# ni.net
KiCad netlist of a schematic drawn in EAGLE
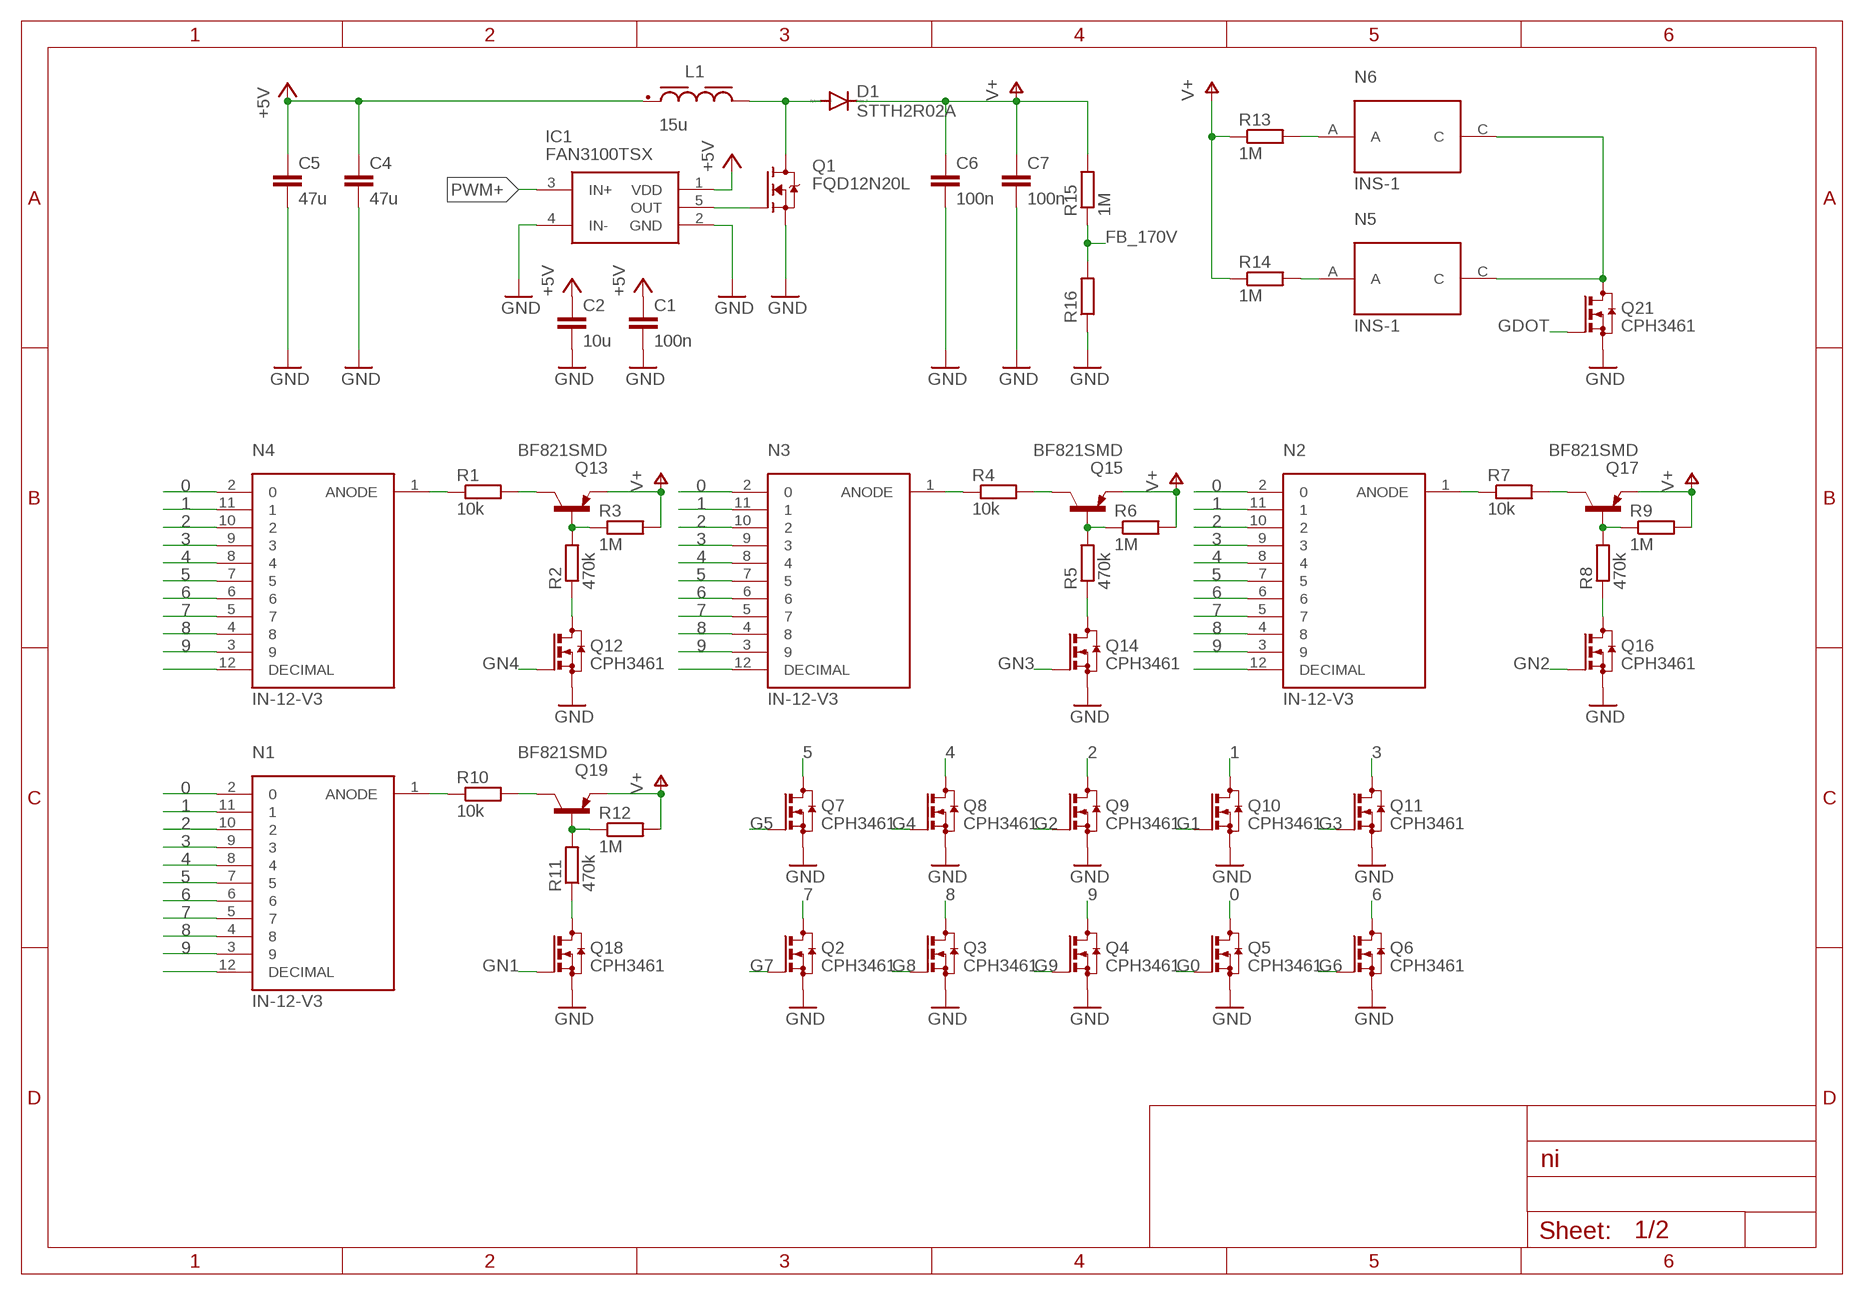
[diagram p0: schematic, sheet 1]
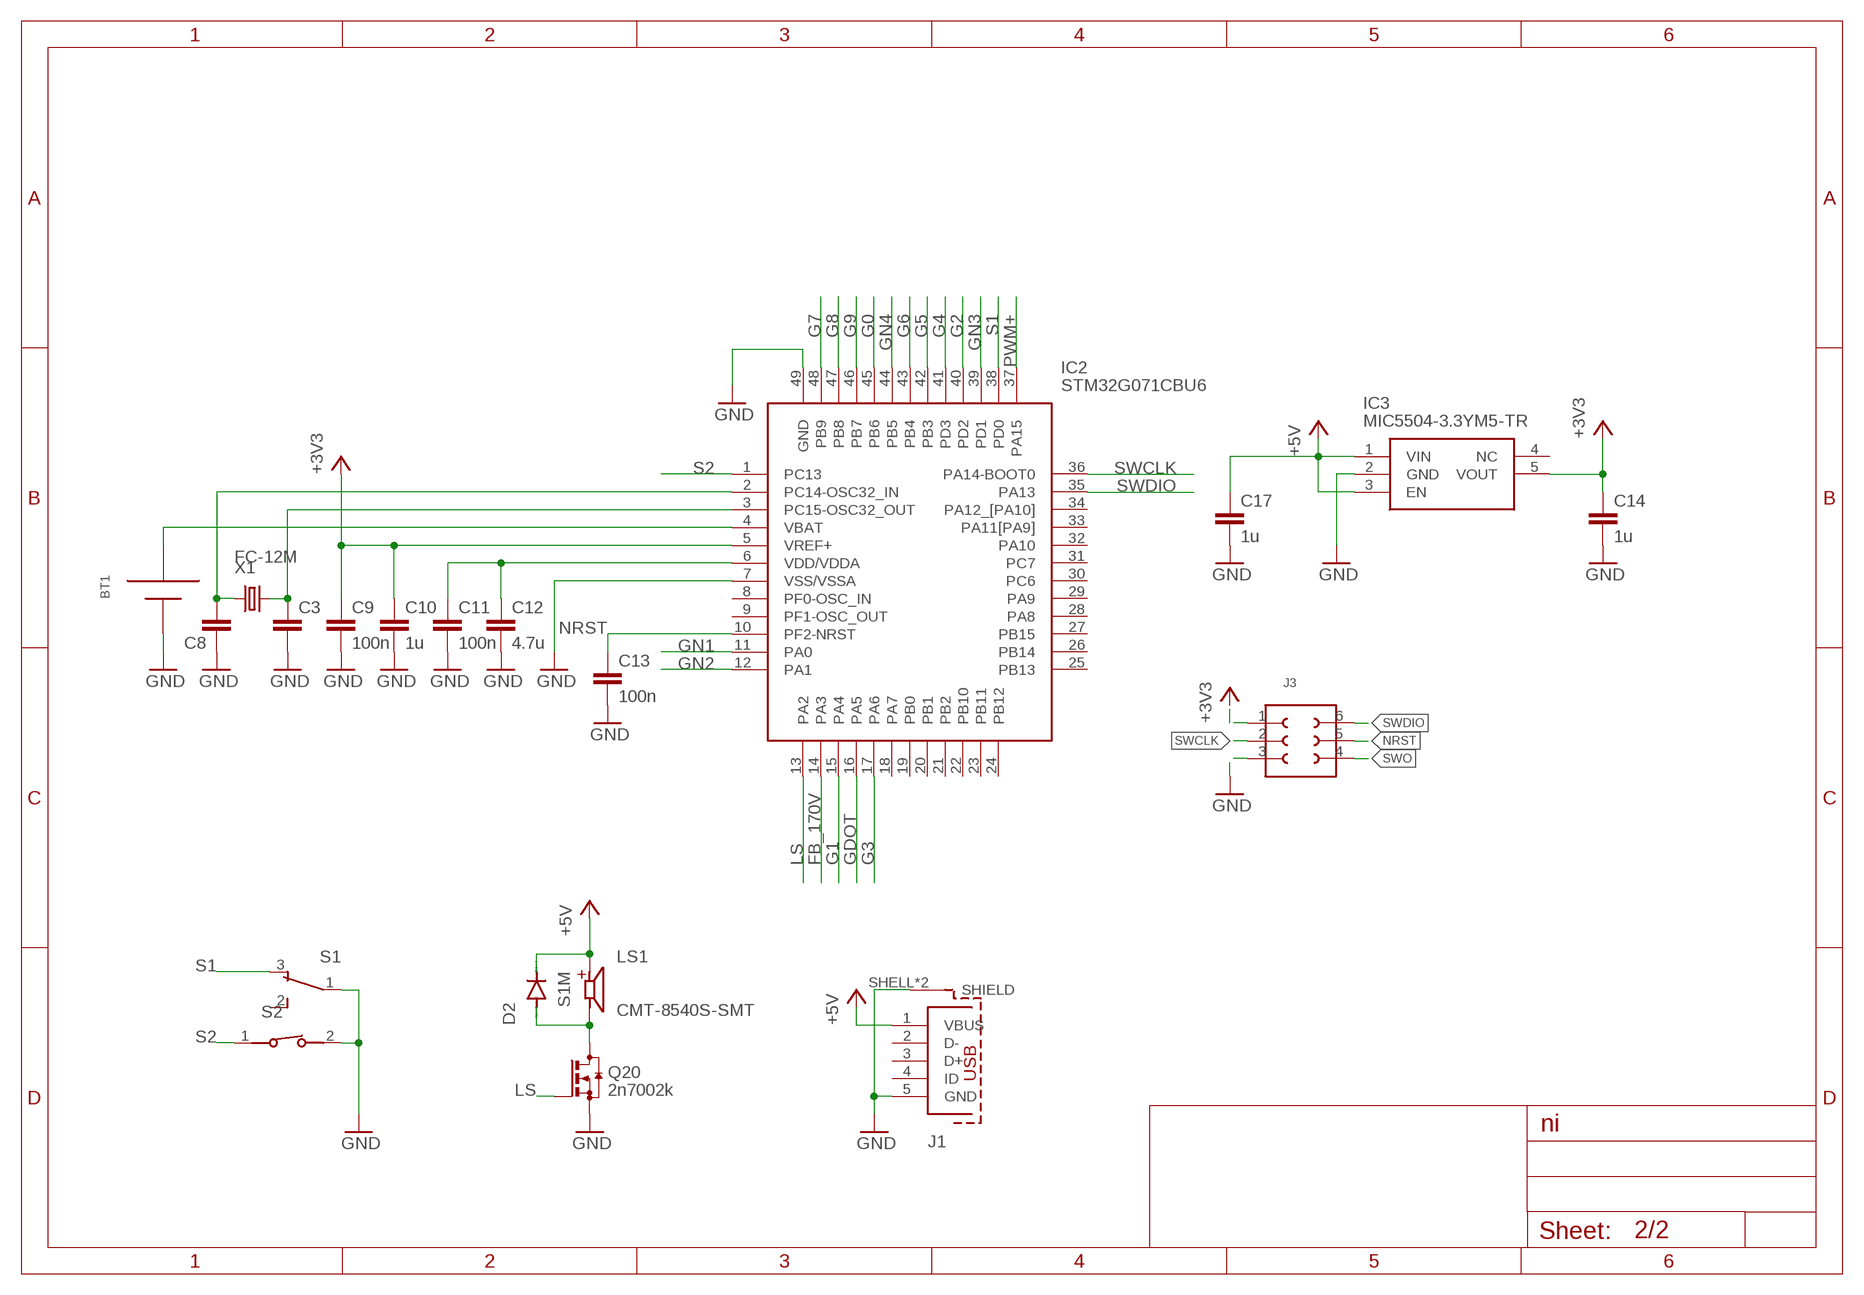
[diagram p1: schematic, sheet 2]

(export (version "E")
  (design (tool "Eeschema 10.0.6"))
  (components
    (comp (ref "BT1")
      (value "CR1225FH-LF")
      (footprint "eagle-import:CR1225FH-LF")
      (libsource (lib "eagle-import") (part "CR1225FH-LF"))
    )
    (comp (ref "C3")
      (value "C-EUC0402")
      (footprint "eagle-import:C0402")
      (libsource (lib "eagle-import") (part "C-EUC0402"))
    )
    (comp (ref "C8")
      (value "C-EUC0402")
      (footprint "eagle-import:C0402")
      (libsource (lib "eagle-import") (part "C-EUC0402"))
    )
    (comp (ref "C9")
      (value "100n")
      (footprint "eagle-import:C0402")
      (libsource (lib "eagle-import") (part "C-EUC0402"))
    )
    (comp (ref "C10")
      (value "1u")
      (footprint "eagle-import:C0402")
      (libsource (lib "eagle-import") (part "C-EUC0402"))
    )
    (comp (ref "C11")
      (value "100n")
      (footprint "eagle-import:C0402")
      (libsource (lib "eagle-import") (part "C-EUC0402"))
    )
    (comp (ref "C12")
      (value "4.7u")
      (footprint "eagle-import:C0402")
      (libsource (lib "eagle-import") (part "C-EUC0402"))
    )
    (comp (ref "C13")
      (value "100n")
      (footprint "eagle-import:C0402")
      (libsource (lib "eagle-import") (part "C-EUC0402"))
    )
    (comp (ref "C14")
      (value "1u")
      (footprint "eagle-import:C0402")
      (libsource (lib "eagle-import") (part "C-EUC0402"))
    )
    (comp (ref "C17")
      (value "1u")
      (footprint "eagle-import:C0603")
      (libsource (lib "eagle-import") (part "C-EUC0603"))
    )
    (comp (ref "D2")
      (value "S1M")
      (footprint "eagle-import:SMA")
      (libsource (lib "eagle-import") (part "S1M"))
    )
    (comp (ref "IC2")
      (value "STM32G071CBU6")
      (footprint "eagle-import:QFN50P700X700X60-49N")
      (fields (field (name "MOUSER_PART_NUMBER") "511-STM32G071CBU6"))
      (libsource (lib "eagle-import") (part "STM32G071CBU6"))
    )
    (comp (ref "IC3")
      (value "MIC5504-3.3YM5-TR")
      (footprint "eagle-import:SOT95P280X145-5N")
      (fields
        (field (name "MOUSER_PART_NUMBER") "998-MIC5504-3.3YM5TR")
        (field (name "RS_PART_NUMBER") "9113332P")
      )
      (libsource (lib "eagle-import") (part "MIC5504-3.3YM5-TR"))
    )
    (comp (ref "J1")
      (value "614105150721")
      (footprint "eagle-import:614105150721")
      (libsource (lib "eagle-import") (part "614105150721"))
    )
    (comp (ref "J3")
      (value "62100621021")
      (footprint "eagle-import:62100621021")
      (libsource (lib "eagle-import") (part "62100621021"))
    )
    (comp (ref "LS1")
      (value "CMT-8540S-SMT")
      (footprint "eagle-import:CUI_CMT-8540S-SMT")
      (fields (field (name "MANUFACTURER") "CUI INC"))
      (libsource (lib "eagle-import") (part "CMT-8540S-SMT"))
    )
    (comp (ref "Q20")
      (value "2n7002k")
      (footprint "eagle-import:SOT23")
      (libsource (lib "eagle-import") (part "BSS123"))
    )
    (comp (ref "S1")
      (value "450301014042")
      (footprint "eagle-import:450301014042")
      (libsource (lib "eagle-import") (part "450301014042"))
    )
    (comp (ref "S2")
      (value "434121050816")
      (footprint "eagle-import:434121050816")
      (libsource (lib "eagle-import") (part "434121050816"))
    )
    (comp (ref "X1")
      (value "FC-12M")
      (footprint "eagle-import:FC-12M")
      (libsource (lib "eagle-import") (part "FC-12M"))
    )
    (comp (ref "C1")
      (value "100n")
      (footprint "eagle-import:C0402")
      (libsource (lib "eagle-import") (part "C-EUC0402"))
    )
    (comp (ref "C2")
      (value "10u")
      (footprint "eagle-import:C1206")
      (libsource (lib "eagle-import") (part "C-EUC1206"))
    )
    (comp (ref "C4")
      (value "47u")
      (footprint "eagle-import:C1206")
      (libsource (lib "eagle-import") (part "C-EUC1206"))
    )
    (comp (ref "C5")
      (value "47u")
      (footprint "eagle-import:C1206")
      (libsource (lib "eagle-import") (part "C-EUC1206"))
    )
    (comp (ref "C6")
      (value "100n")
      (footprint "eagle-import:C1812")
      (libsource (lib "eagle-import") (part "C-EUC1812"))
    )
    (comp (ref "C7")
      (value "100n")
      (footprint "eagle-import:C1812")
      (libsource (lib "eagle-import") (part "C-EUC1812"))
    )
    (comp (ref "D1")
      (value "STTH2R02A")
      (footprint "eagle-import:DO214AC")
      (libsource (lib "eagle-import") (part "DIODE-DO214AC"))
    )
    (comp (ref "IC1")
      (value "FAN3100TSX")
      (footprint "eagle-import:SOT95P280X145-5N")
      (fields (field (name "MOUSER_PART_NUMBER") "512-FAN3100TSX"))
      (libsource (lib "eagle-import") (part "FAN3100TSX"))
    )
    (comp (ref "L1")
      (value "15u")
      (footprint "eagle-import:WE-LQS_5040")
      (libsource (lib "eagle-import") (part "WE-LQS_5040_74404054150"))
    )
    (comp (ref "N1")
      (value "IN-12-V3")
      (footprint "eagle-import:IN-12")
      (libsource (lib "eagle-import") (part "IN-12-V3"))
    )
    (comp (ref "N2")
      (value "IN-12-V3")
      (footprint "eagle-import:IN-12")
      (libsource (lib "eagle-import") (part "IN-12-V3"))
    )
    (comp (ref "N3")
      (value "IN-12-V3")
      (footprint "eagle-import:IN-12")
      (libsource (lib "eagle-import") (part "IN-12-V3"))
    )
    (comp (ref "N4")
      (value "IN-12-V3")
      (footprint "eagle-import:IN-12")
      (libsource (lib "eagle-import") (part "IN-12-V3"))
    )
    (comp (ref "N5")
      (value "INS-1")
      (footprint "eagle-import:INS-1")
      (libsource (lib "eagle-import") (part "INS-1"))
    )
    (comp (ref "N6")
      (value "INS-1")
      (footprint "eagle-import:INS-1")
      (libsource (lib "eagle-import") (part "INS-1"))
    )
    (comp (ref "Q1")
      (value "FQD12N20L")
      (footprint "eagle-import:TO229P990X240-3N")
      (libsource (lib "eagle-import") (part "FQD12N20L"))
    )
    (comp (ref "Q2")
      (value "CPH3461")
      (footprint "eagle-import:SOT23")
      (libsource (lib "eagle-import") (part "BSS123"))
    )
    (comp (ref "Q3")
      (value "CPH3461")
      (footprint "eagle-import:SOT23")
      (libsource (lib "eagle-import") (part "BSS123"))
    )
    (comp (ref "Q4")
      (value "CPH3461")
      (footprint "eagle-import:SOT23")
      (libsource (lib "eagle-import") (part "BSS123"))
    )
    (comp (ref "Q5")
      (value "CPH3461")
      (footprint "eagle-import:SOT23")
      (libsource (lib "eagle-import") (part "BSS123"))
    )
    (comp (ref "Q6")
      (value "CPH3461")
      (footprint "eagle-import:SOT23")
      (libsource (lib "eagle-import") (part "BSS123"))
    )
    (comp (ref "Q7")
      (value "CPH3461")
      (footprint "eagle-import:SOT23")
      (libsource (lib "eagle-import") (part "BSS123"))
    )
    (comp (ref "Q8")
      (value "CPH3461")
      (footprint "eagle-import:SOT23")
      (libsource (lib "eagle-import") (part "BSS123"))
    )
    (comp (ref "Q9")
      (value "CPH3461")
      (footprint "eagle-import:SOT23")
      (libsource (lib "eagle-import") (part "BSS123"))
    )
    (comp (ref "Q10")
      (value "CPH3461")
      (footprint "eagle-import:SOT23")
      (libsource (lib "eagle-import") (part "BSS123"))
    )
    (comp (ref "Q11")
      (value "CPH3461")
      (footprint "eagle-import:SOT23")
      (libsource (lib "eagle-import") (part "BSS123"))
    )
    (comp (ref "Q12")
      (value "CPH3461")
      (footprint "eagle-import:SOT23")
      (libsource (lib "eagle-import") (part "BSS123"))
    )
    (comp (ref "Q13")
      (value "BF821SMD")
      (footprint "eagle-import:SOT23-BEC")
      (libsource (lib "eagle-import") (part "BF821SMD"))
    )
    (comp (ref "Q14")
      (value "CPH3461")
      (footprint "eagle-import:SOT23")
      (libsource (lib "eagle-import") (part "BSS123"))
    )
    (comp (ref "Q15")
      (value "BF821SMD")
      (footprint "eagle-import:SOT23-BEC")
      (libsource (lib "eagle-import") (part "BF821SMD"))
    )
    (comp (ref "Q16")
      (value "CPH3461")
      (footprint "eagle-import:SOT23")
      (libsource (lib "eagle-import") (part "BSS123"))
    )
    (comp (ref "Q17")
      (value "BF821SMD")
      (footprint "eagle-import:SOT23-BEC")
      (libsource (lib "eagle-import") (part "BF821SMD"))
    )
    (comp (ref "Q18")
      (value "CPH3461")
      (footprint "eagle-import:SOT23")
      (libsource (lib "eagle-import") (part "BSS123"))
    )
    (comp (ref "Q19")
      (value "BF821SMD")
      (footprint "eagle-import:SOT23-BEC")
      (libsource (lib "eagle-import") (part "BF821SMD"))
    )
    (comp (ref "Q21")
      (value "CPH3461")
      (footprint "eagle-import:SOT23")
      (libsource (lib "eagle-import") (part "BSS123"))
    )
    (comp (ref "R1")
      (value "10k")
      (footprint "eagle-import:R1206")
      (libsource (lib "eagle-import") (part "R-EU_R1206"))
    )
    (comp (ref "R2")
      (value "470k")
      (footprint "eagle-import:R1206")
      (libsource (lib "eagle-import") (part "R-EU_R1206"))
    )
    (comp (ref "R3")
      (value "1M")
      (footprint "eagle-import:R1206")
      (libsource (lib "eagle-import") (part "R-EU_R1206"))
    )
    (comp (ref "R4")
      (value "10k")
      (footprint "eagle-import:R1206")
      (libsource (lib "eagle-import") (part "R-EU_R1206"))
    )
    (comp (ref "R5")
      (value "470k")
      (footprint "eagle-import:R1206")
      (libsource (lib "eagle-import") (part "R-EU_R1206"))
    )
    (comp (ref "R6")
      (value "1M")
      (footprint "eagle-import:R1206")
      (libsource (lib "eagle-import") (part "R-EU_R1206"))
    )
    (comp (ref "R7")
      (value "10k")
      (footprint "eagle-import:R1206")
      (libsource (lib "eagle-import") (part "R-EU_R1206"))
    )
    (comp (ref "R8")
      (value "470k")
      (footprint "eagle-import:R1206")
      (libsource (lib "eagle-import") (part "R-EU_R1206"))
    )
    (comp (ref "R9")
      (value "1M")
      (footprint "eagle-import:R1206")
      (libsource (lib "eagle-import") (part "R-EU_R1206"))
    )
    (comp (ref "R10")
      (value "10k")
      (footprint "eagle-import:R1206")
      (libsource (lib "eagle-import") (part "R-EU_R1206"))
    )
    (comp (ref "R11")
      (value "470k")
      (footprint "eagle-import:R1206")
      (libsource (lib "eagle-import") (part "R-EU_R1206"))
    )
    (comp (ref "R12")
      (value "1M")
      (footprint "eagle-import:R1206")
      (libsource (lib "eagle-import") (part "R-EU_R1206"))
    )
    (comp (ref "R13")
      (value "1M")
      (footprint "eagle-import:R2010")
      (libsource (lib "eagle-import") (part "R-EU_R2010"))
    )
    (comp (ref "R14")
      (value "1M")
      (footprint "eagle-import:R2010")
      (libsource (lib "eagle-import") (part "R-EU_R2010"))
    )
    (comp (ref "R15")
      (value "1M")
      (footprint "eagle-import:R1206")
      (libsource (lib "eagle-import") (part "R-EU_R1206"))
    )
    (comp (ref "R16")
      (value "R-EU_R0402")
      (footprint "eagle-import:R0402")
      (libsource (lib "eagle-import") (part "R-EU_R0402"))
    )
  )
  (nets
    (net (code "1") (name "+3V3") (class "Default")
      (node (ref "C10") (pin "1") (pinfunction "1_1") (pintype "passive"))
      (node (ref "C14") (pin "1") (pinfunction "1_1") (pintype "passive"))
      (node (ref "C9") (pin "1") (pinfunction "1_1") (pintype "passive"))
      (node (ref "IC2") (pin "5") (pinfunction "VREF+_5") (pintype "bidirectional"))
      (node (ref "IC3") (pin "5") (pinfunction "VOUT_5") (pintype "bidirectional"))
      (node (ref "J3") (pin "1") (pinfunction "1_1") (pintype "passive"))
    )
    (net (code "2") (name "+5V") (class "Default")
      (node (ref "C1") (pin "1") (pinfunction "1_1") (pintype "passive"))
      (node (ref "C17") (pin "1") (pinfunction "1_1") (pintype "passive"))
      (node (ref "C2") (pin "1") (pinfunction "1_1") (pintype "passive"))
      (node (ref "C4") (pin "1") (pinfunction "1_1") (pintype "passive"))
      (node (ref "C5") (pin "1") (pinfunction "1_1") (pintype "passive"))
      (node (ref "D2") (pin "C") (pinfunction "C_C") (pintype "passive"))
      (node (ref "IC1") (pin "1") (pinfunction "VDD_1") (pintype "bidirectional"))
      (node (ref "IC3") (pin "1") (pinfunction "VIN_1") (pintype "bidirectional"))
      (node (ref "IC3") (pin "3") (pinfunction "EN_3") (pintype "bidirectional"))
      (node (ref "J1") (pin "1") (pinfunction "VBUS_1") (pintype "passive"))
      (node (ref "L1") (pin "1") (pinfunction "1_1") (pintype "passive"))
      (node (ref "LS1") (pin "P") (pinfunction "P_P") (pintype "passive"))
    )
    (net (code "3") (name "0") (class "Default")
      (node (ref "N1") (pin "2") (pinfunction "0_2") (pintype "bidirectional"))
      (node (ref "N2") (pin "2") (pinfunction "0_2") (pintype "bidirectional"))
      (node (ref "N3") (pin "2") (pinfunction "0_2") (pintype "bidirectional"))
      (node (ref "N4") (pin "2") (pinfunction "0_2") (pintype "bidirectional"))
      (node (ref "Q5") (pin "3") (pinfunction "D_3") (pintype "passive"))
    )
    (net (code "4") (name "1") (class "Default")
      (node (ref "N1") (pin "11") (pinfunction "1_11") (pintype "bidirectional"))
      (node (ref "N2") (pin "11") (pinfunction "1_11") (pintype "bidirectional"))
      (node (ref "N3") (pin "11") (pinfunction "1_11") (pintype "bidirectional"))
      (node (ref "N4") (pin "11") (pinfunction "1_11") (pintype "bidirectional"))
      (node (ref "Q10") (pin "3") (pinfunction "D_3") (pintype "passive"))
    )
    (net (code "5") (name "2") (class "Default")
      (node (ref "N1") (pin "10") (pinfunction "2_10") (pintype "bidirectional"))
      (node (ref "N2") (pin "10") (pinfunction "2_10") (pintype "bidirectional"))
      (node (ref "N3") (pin "10") (pinfunction "2_10") (pintype "bidirectional"))
      (node (ref "N4") (pin "10") (pinfunction "2_10") (pintype "bidirectional"))
      (node (ref "Q9") (pin "3") (pinfunction "D_3") (pintype "passive"))
    )
    (net (code "6") (name "3") (class "Default")
      (node (ref "N1") (pin "9") (pinfunction "3_9") (pintype "bidirectional"))
      (node (ref "N2") (pin "9") (pinfunction "3_9") (pintype "bidirectional"))
      (node (ref "N3") (pin "9") (pinfunction "3_9") (pintype "bidirectional"))
      (node (ref "N4") (pin "9") (pinfunction "3_9") (pintype "bidirectional"))
      (node (ref "Q11") (pin "3") (pinfunction "D_3") (pintype "passive"))
    )
    (net (code "7") (name "4") (class "Default")
      (node (ref "N1") (pin "8") (pinfunction "4_8") (pintype "bidirectional"))
      (node (ref "N2") (pin "8") (pinfunction "4_8") (pintype "bidirectional"))
      (node (ref "N3") (pin "8") (pinfunction "4_8") (pintype "bidirectional"))
      (node (ref "N4") (pin "8") (pinfunction "4_8") (pintype "bidirectional"))
      (node (ref "Q8") (pin "3") (pinfunction "D_3") (pintype "passive"))
    )
    (net (code "8") (name "5") (class "Default")
      (node (ref "N1") (pin "7") (pinfunction "5_7") (pintype "bidirectional"))
      (node (ref "N2") (pin "7") (pinfunction "5_7") (pintype "bidirectional"))
      (node (ref "N3") (pin "7") (pinfunction "5_7") (pintype "bidirectional"))
      (node (ref "N4") (pin "7") (pinfunction "5_7") (pintype "bidirectional"))
      (node (ref "Q7") (pin "3") (pinfunction "D_3") (pintype "passive"))
    )
    (net (code "9") (name "6") (class "Default")
      (node (ref "N1") (pin "6") (pinfunction "6_6") (pintype "bidirectional"))
      (node (ref "N2") (pin "6") (pinfunction "6_6") (pintype "bidirectional"))
      (node (ref "N3") (pin "6") (pinfunction "6_6") (pintype "bidirectional"))
      (node (ref "N4") (pin "6") (pinfunction "6_6") (pintype "bidirectional"))
      (node (ref "Q6") (pin "3") (pinfunction "D_3") (pintype "passive"))
    )
    (net (code "10") (name "7") (class "Default")
      (node (ref "N1") (pin "5") (pinfunction "7_5") (pintype "bidirectional"))
      (node (ref "N2") (pin "5") (pinfunction "7_5") (pintype "bidirectional"))
      (node (ref "N3") (pin "5") (pinfunction "7_5") (pintype "bidirectional"))
      (node (ref "N4") (pin "5") (pinfunction "7_5") (pintype "bidirectional"))
      (node (ref "Q2") (pin "3") (pinfunction "D_3") (pintype "passive"))
    )
    (net (code "11") (name "8") (class "Default")
      (node (ref "N1") (pin "4") (pinfunction "8_4") (pintype "bidirectional"))
      (node (ref "N2") (pin "4") (pinfunction "8_4") (pintype "bidirectional"))
      (node (ref "N3") (pin "4") (pinfunction "8_4") (pintype "bidirectional"))
      (node (ref "N4") (pin "4") (pinfunction "8_4") (pintype "bidirectional"))
      (node (ref "Q3") (pin "3") (pinfunction "D_3") (pintype "passive"))
    )
    (net (code "12") (name "9") (class "Default")
      (node (ref "N1") (pin "3") (pinfunction "9_3") (pintype "bidirectional"))
      (node (ref "N2") (pin "3") (pinfunction "9_3") (pintype "bidirectional"))
      (node (ref "N3") (pin "3") (pinfunction "9_3") (pintype "bidirectional"))
      (node (ref "N4") (pin "3") (pinfunction "9_3") (pintype "bidirectional"))
      (node (ref "Q4") (pin "3") (pinfunction "D_3") (pintype "passive"))
    )
    (net (code "13") (name "FB_170V") (class "Default")
      (node (ref "IC2") (pin "14") (pinfunction "PA3_14") (pintype "bidirectional"))
      (node (ref "R15") (pin "1") (pinfunction "1_1") (pintype "passive"))
      (node (ref "R16") (pin "2") (pinfunction "2_2") (pintype "passive"))
    )
    (net (code "14") (name "G0") (class "Default")
      (node (ref "IC2") (pin "45") (pinfunction "PB6_45") (pintype "bidirectional"))
      (node (ref "Q5") (pin "1") (pinfunction "G_1") (pintype "passive"))
    )
    (net (code "15") (name "G1") (class "Default")
      (node (ref "IC2") (pin "15") (pinfunction "PA4_15") (pintype "bidirectional"))
      (node (ref "Q10") (pin "1") (pinfunction "G_1") (pintype "passive"))
    )
    (net (code "16") (name "G2") (class "Default")
      (node (ref "IC2") (pin "40") (pinfunction "PD2_40") (pintype "bidirectional"))
      (node (ref "Q9") (pin "1") (pinfunction "G_1") (pintype "passive"))
    )
    (net (code "17") (name "G3") (class "Default")
      (node (ref "IC2") (pin "17") (pinfunction "PA6_17") (pintype "bidirectional"))
      (node (ref "Q11") (pin "1") (pinfunction "G_1") (pintype "passive"))
    )
    (net (code "18") (name "G4") (class "Default")
      (node (ref "IC2") (pin "41") (pinfunction "PD3_41") (pintype "bidirectional"))
      (node (ref "Q8") (pin "1") (pinfunction "G_1") (pintype "passive"))
    )
    (net (code "19") (name "G5") (class "Default")
      (node (ref "IC2") (pin "42") (pinfunction "PB3_42") (pintype "bidirectional"))
      (node (ref "Q7") (pin "1") (pinfunction "G_1") (pintype "passive"))
    )
    (net (code "20") (name "G6") (class "Default")
      (node (ref "IC2") (pin "43") (pinfunction "PB4_43") (pintype "bidirectional"))
      (node (ref "Q6") (pin "1") (pinfunction "G_1") (pintype "passive"))
    )
    (net (code "21") (name "G7") (class "Default")
      (node (ref "IC2") (pin "48") (pinfunction "PB9_48") (pintype "bidirectional"))
      (node (ref "Q2") (pin "1") (pinfunction "G_1") (pintype "passive"))
    )
    (net (code "22") (name "G8") (class "Default")
      (node (ref "IC2") (pin "47") (pinfunction "PB8_47") (pintype "bidirectional"))
      (node (ref "Q3") (pin "1") (pinfunction "G_1") (pintype "passive"))
    )
    (net (code "23") (name "G9") (class "Default")
      (node (ref "IC2") (pin "46") (pinfunction "PB7_46") (pintype "bidirectional"))
      (node (ref "Q4") (pin "1") (pinfunction "G_1") (pintype "passive"))
    )
    (net (code "24") (name "GDOT") (class "Default")
      (node (ref "IC2") (pin "16") (pinfunction "PA5_16") (pintype "bidirectional"))
      (node (ref "Q21") (pin "1") (pinfunction "G_1") (pintype "passive"))
    )
    (net (code "25") (name "GN1") (class "Default")
      (node (ref "IC2") (pin "11") (pinfunction "PA0_11") (pintype "bidirectional"))
      (node (ref "Q18") (pin "1") (pinfunction "G_1") (pintype "passive"))
    )
    (net (code "26") (name "GN2") (class "Default")
      (node (ref "IC2") (pin "12") (pinfunction "PA1_12") (pintype "bidirectional"))
      (node (ref "Q16") (pin "1") (pinfunction "G_1") (pintype "passive"))
    )
    (net (code "27") (name "GN3") (class "Default")
      (node (ref "IC2") (pin "39") (pinfunction "PD1_39") (pintype "bidirectional"))
      (node (ref "Q14") (pin "1") (pinfunction "G_1") (pintype "passive"))
    )
    (net (code "28") (name "GN4") (class "Default")
      (node (ref "IC2") (pin "44") (pinfunction "PB5_44") (pintype "bidirectional"))
      (node (ref "Q12") (pin "1") (pinfunction "G_1") (pintype "passive"))
    )
    (net (code "29") (name "GND") (class "Default")
      (node (ref "BT1") (pin "-") (pinfunction "-_-") (pintype "output"))
      (node (ref "C1") (pin "2") (pinfunction "2_2") (pintype "passive"))
      (node (ref "C10") (pin "2") (pinfunction "2_2") (pintype "passive"))
      (node (ref "C11") (pin "2") (pinfunction "2_2") (pintype "passive"))
      (node (ref "C12") (pin "2") (pinfunction "2_2") (pintype "passive"))
      (node (ref "C13") (pin "2") (pinfunction "2_2") (pintype "passive"))
      (node (ref "C14") (pin "2") (pinfunction "2_2") (pintype "passive"))
      (node (ref "C17") (pin "2") (pinfunction "2_2") (pintype "passive"))
      (node (ref "C2") (pin "2") (pinfunction "2_2") (pintype "passive"))
      (node (ref "C3") (pin "2") (pinfunction "2_2") (pintype "passive"))
      (node (ref "C4") (pin "2") (pinfunction "2_2") (pintype "passive"))
      (node (ref "C5") (pin "2") (pinfunction "2_2") (pintype "passive"))
      (node (ref "C6") (pin "2") (pinfunction "2_2") (pintype "passive"))
      (node (ref "C7") (pin "2") (pinfunction "2_2") (pintype "passive"))
      (node (ref "C8") (pin "1") (pinfunction "1_1") (pintype "passive"))
      (node (ref "C9") (pin "2") (pinfunction "2_2") (pintype "passive"))
      (node (ref "IC1") (pin "2") (pinfunction "GND_2") (pintype "bidirectional"))
      (node (ref "IC1") (pin "4") (pinfunction "IN-_4") (pintype "bidirectional"))
      (node (ref "IC2") (pin "49") (pinfunction "GND_49") (pintype "bidirectional"))
      (node (ref "IC2") (pin "7") (pinfunction "VSS/VSSA_7") (pintype "bidirectional"))
      (node (ref "IC3") (pin "2") (pinfunction "GND_2") (pintype "bidirectional"))
      (node (ref "J1") (pin "5") (pinfunction "GND_5") (pintype "passive"))
      (node (ref "J1") (pin "SHELL") (pinfunction "SHIELD_SHELL") (pintype "passive"))
      (node (ref "J1") (pin "SHELL1") (pinfunction "SHIELD_SHELL1") (pintype "passive"))
      (node (ref "J3") (pin "3") (pinfunction "3_3") (pintype "passive"))
      (node (ref "Q1") (pin "2") (pinfunction "S_2") (pintype "passive"))
      (node (ref "Q10") (pin "2") (pinfunction "S_2") (pintype "passive"))
      (node (ref "Q11") (pin "2") (pinfunction "S_2") (pintype "passive"))
      (node (ref "Q12") (pin "2") (pinfunction "S_2") (pintype "passive"))
      (node (ref "Q14") (pin "2") (pinfunction "S_2") (pintype "passive"))
      (node (ref "Q16") (pin "2") (pinfunction "S_2") (pintype "passive"))
      (node (ref "Q18") (pin "2") (pinfunction "S_2") (pintype "passive"))
      (node (ref "Q2") (pin "2") (pinfunction "S_2") (pintype "passive"))
      (node (ref "Q20") (pin "2") (pinfunction "S_2") (pintype "passive"))
      (node (ref "Q21") (pin "2") (pinfunction "S_2") (pintype "passive"))
      (node (ref "Q3") (pin "2") (pinfunction "S_2") (pintype "passive"))
      (node (ref "Q4") (pin "2") (pinfunction "S_2") (pintype "passive"))
      (node (ref "Q5") (pin "2") (pinfunction "S_2") (pintype "passive"))
      (node (ref "Q6") (pin "2") (pinfunction "S_2") (pintype "passive"))
      (node (ref "Q7") (pin "2") (pinfunction "S_2") (pintype "passive"))
      (node (ref "Q8") (pin "2") (pinfunction "S_2") (pintype "passive"))
      (node (ref "Q9") (pin "2") (pinfunction "S_2") (pintype "passive"))
      (node (ref "R16") (pin "1") (pinfunction "1_1") (pintype "passive"))
      (node (ref "S1") (pin "1") (pinfunction "1_1") (pintype "passive"))
      (node (ref "S2") (pin "2") (pinfunction "2_2") (pintype "passive"))
    )
    (net (code "30") (name "LS") (class "Default")
      (node (ref "IC2") (pin "13") (pinfunction "PA2_13") (pintype "bidirectional"))
      (node (ref "Q20") (pin "1") (pinfunction "G_1") (pintype "passive"))
    )
    (net (code "31") (name "NRST") (class "Default")
      (node (ref "C13") (pin "1") (pinfunction "1_1") (pintype "passive"))
      (node (ref "IC2") (pin "10") (pinfunction "PF2-NRST_10") (pintype "bidirectional"))
      (node (ref "J3") (pin "5") (pinfunction "5_5") (pintype "passive"))
    )
    (net (code "32") (name "Net-(IC1-OUT)") (class "Default")
      (node (ref "IC1") (pin "5") (pinfunction "OUT_5") (pintype "bidirectional"))
      (node (ref "Q1") (pin "1") (pinfunction "G_1") (pintype "passive"))
    )
    (net (code "33") (name "Net-(IC2-PC14-OSC32_IN)") (class "Default")
      (node (ref "C8") (pin "2") (pinfunction "2_2") (pintype "passive"))
      (node (ref "IC2") (pin "2") (pinfunction "PC14-OSC32_IN_2") (pintype "bidirectional"))
      (node (ref "X1") (pin "1") (pinfunction "1_1") (pintype "passive"))
    )
    (net (code "34") (name "Net-(IC2-PC15-OSC32_OUT)") (class "Default")
      (node (ref "C3") (pin "1") (pinfunction "1_1") (pintype "passive"))
      (node (ref "IC2") (pin "3") (pinfunction "PC15-OSC32_OUT_3") (pintype "bidirectional"))
      (node (ref "X1") (pin "2") (pinfunction "2_2") (pintype "passive"))
    )
    (net (code "35") (name "Net-(IC2-VBAT)") (class "Default")
      (node (ref "BT1") (pin "+") (pinfunction "+_+") (pintype "output"))
      (node (ref "IC2") (pin "4") (pinfunction "VBAT_4") (pintype "bidirectional"))
    )
    (net (code "36") (name "Net-(IC2-VDD{slash}VDDA)") (class "Default")
      (node (ref "C11") (pin "1") (pinfunction "1_1") (pintype "passive"))
      (node (ref "C12") (pin "1") (pinfunction "1_1") (pintype "passive"))
      (node (ref "IC2") (pin "6") (pinfunction "VDD/VDDA_6") (pintype "bidirectional"))
    )
    (net (code "37") (name "Net-(N1-ANODE)") (class "Default")
      (node (ref "N1") (pin "1") (pinfunction "ANODE_1") (pintype "bidirectional"))
      (node (ref "R10") (pin "1") (pinfunction "1_1") (pintype "passive"))
    )
    (net (code "38") (name "Net-(N2-ANODE)") (class "Default")
      (node (ref "N2") (pin "1") (pinfunction "ANODE_1") (pintype "bidirectional"))
      (node (ref "R7") (pin "1") (pinfunction "1_1") (pintype "passive"))
    )
    (net (code "39") (name "Net-(N3-ANODE)") (class "Default")
      (node (ref "N3") (pin "1") (pinfunction "ANODE_1") (pintype "bidirectional"))
      (node (ref "R4") (pin "1") (pinfunction "1_1") (pintype "passive"))
    )
    (net (code "40") (name "Net-(N4-ANODE)") (class "Default")
      (node (ref "N4") (pin "1") (pinfunction "ANODE_1") (pintype "bidirectional"))
      (node (ref "R1") (pin "1") (pinfunction "1_1") (pintype "passive"))
    )
    (net (code "41") (name "Net-(N5-PadA)") (class "Default")
      (node (ref "N5") (pin "A") (pinfunction "A_A") (pintype "bidirectional"))
      (node (ref "R14") (pin "2") (pinfunction "2_2") (pintype "passive"))
    )
    (net (code "42") (name "Net-(N6-PadA)") (class "Default")
      (node (ref "N6") (pin "A") (pinfunction "A_A") (pintype "bidirectional"))
      (node (ref "R13") (pin "2") (pinfunction "2_2") (pintype "passive"))
    )
    (net (code "43") (name "Net-(Q1-D)") (class "Default")
      (node (ref "D1") (pin "A") (pinfunction "A_A") (pintype "passive"))
      (node (ref "L1") (pin "2") (pinfunction "2_2") (pintype "passive"))
      (node (ref "Q1") (pin "3") (pinfunction "D_3") (pintype "passive"))
    )
    (net (code "44") (name "Net-(Q12-D)") (class "Default")
      (node (ref "Q12") (pin "3") (pinfunction "D_3") (pintype "passive"))
      (node (ref "R2") (pin "1") (pinfunction "1_1") (pintype "passive"))
    )
    (net (code "45") (name "Net-(Q13-PadB)") (class "Default")
      (node (ref "Q13") (pin "B") (pinfunction "B_B") (pintype "passive"))
      (node (ref "R2") (pin "2") (pinfunction "2_2") (pintype "passive"))
      (node (ref "R3") (pin "1") (pinfunction "1_1") (pintype "passive"))
    )
    (net (code "46") (name "Net-(Q13-PadC)") (class "Default")
      (node (ref "Q13") (pin "C") (pinfunction "C_C") (pintype "passive"))
      (node (ref "R1") (pin "2") (pinfunction "2_2") (pintype "passive"))
    )
    (net (code "47") (name "Net-(Q14-D)") (class "Default")
      (node (ref "Q14") (pin "3") (pinfunction "D_3") (pintype "passive"))
      (node (ref "R5") (pin "1") (pinfunction "1_1") (pintype "passive"))
    )
    (net (code "48") (name "Net-(Q15-PadB)") (class "Default")
      (node (ref "Q15") (pin "B") (pinfunction "B_B") (pintype "passive"))
      (node (ref "R5") (pin "2") (pinfunction "2_2") (pintype "passive"))
      (node (ref "R6") (pin "1") (pinfunction "1_1") (pintype "passive"))
    )
    (net (code "49") (name "Net-(Q15-PadC)") (class "Default")
      (node (ref "Q15") (pin "C") (pinfunction "C_C") (pintype "passive"))
      (node (ref "R4") (pin "2") (pinfunction "2_2") (pintype "passive"))
    )
    (net (code "50") (name "Net-(Q16-D)") (class "Default")
      (node (ref "Q16") (pin "3") (pinfunction "D_3") (pintype "passive"))
      (node (ref "R8") (pin "1") (pinfunction "1_1") (pintype "passive"))
    )
    (net (code "51") (name "Net-(Q17-PadB)") (class "Default")
      (node (ref "Q17") (pin "B") (pinfunction "B_B") (pintype "passive"))
      (node (ref "R8") (pin "2") (pinfunction "2_2") (pintype "passive"))
      (node (ref "R9") (pin "1") (pinfunction "1_1") (pintype "passive"))
    )
    (net (code "52") (name "Net-(Q17-PadC)") (class "Default")
      (node (ref "Q17") (pin "C") (pinfunction "C_C") (pintype "passive"))
      (node (ref "R7") (pin "2") (pinfunction "2_2") (pintype "passive"))
    )
    (net (code "53") (name "Net-(Q18-D)") (class "Default")
      (node (ref "Q18") (pin "3") (pinfunction "D_3") (pintype "passive"))
      (node (ref "R11") (pin "1") (pinfunction "1_1") (pintype "passive"))
    )
    (net (code "54") (name "Net-(Q19-PadB)") (class "Default")
      (node (ref "Q19") (pin "B") (pinfunction "B_B") (pintype "passive"))
      (node (ref "R11") (pin "2") (pinfunction "2_2") (pintype "passive"))
      (node (ref "R12") (pin "1") (pinfunction "1_1") (pintype "passive"))
    )
    (net (code "55") (name "Net-(Q19-PadC)") (class "Default")
      (node (ref "Q19") (pin "C") (pinfunction "C_C") (pintype "passive"))
      (node (ref "R10") (pin "2") (pinfunction "2_2") (pintype "passive"))
    )
    (net (code "56") (name "Net-(Q20-D)") (class "Default")
      (node (ref "D2") (pin "A") (pinfunction "A_A") (pintype "passive"))
      (node (ref "LS1") (pin "N") (pinfunction "N_N") (pintype "passive"))
      (node (ref "Q20") (pin "3") (pinfunction "D_3") (pintype "passive"))
    )
    (net (code "57") (name "Net-(Q21-D)") (class "Default")
      (node (ref "N5") (pin "C") (pinfunction "C_C") (pintype "bidirectional"))
      (node (ref "N6") (pin "C") (pinfunction "C_C") (pintype "bidirectional"))
      (node (ref "Q21") (pin "3") (pinfunction "D_3") (pintype "passive"))
    )
    (net (code "58") (name "PWM+") (class "Default")
      (node (ref "IC1") (pin "3") (pinfunction "IN+_3") (pintype "bidirectional"))
      (node (ref "IC2") (pin "37") (pinfunction "PA15_37") (pintype "bidirectional"))
    )
    (net (code "59") (name "S1") (class "Default")
      (node (ref "IC2") (pin "38") (pinfunction "PD0_38") (pintype "bidirectional"))
      (node (ref "S1") (pin "3") (pinfunction "3_3") (pintype "passive"))
    )
    (net (code "60") (name "S2") (class "Default")
      (node (ref "IC2") (pin "1") (pinfunction "PC13_1") (pintype "bidirectional"))
      (node (ref "S2") (pin "1") (pinfunction "1_1") (pintype "passive"))
    )
    (net (code "61") (name "SWCLK") (class "Default")
      (node (ref "IC2") (pin "36") (pinfunction "PA14-BOOT0_36") (pintype "bidirectional"))
      (node (ref "J3") (pin "2") (pinfunction "2_2") (pintype "passive"))
    )
    (net (code "62") (name "SWDIO") (class "Default")
      (node (ref "IC2") (pin "35") (pinfunction "PA13_35") (pintype "bidirectional"))
      (node (ref "J3") (pin "6") (pinfunction "6_6") (pintype "passive"))
    )
    (net (code "63") (name "SWO") (class "Default")
      (node (ref "J3") (pin "4") (pinfunction "4_4") (pintype "passive"))
    )
    (net (code "64") (name "V+") (class "Default")
      (node (ref "C6") (pin "1") (pinfunction "1_1") (pintype "passive"))
      (node (ref "C7") (pin "1") (pinfunction "1_1") (pintype "passive"))
      (node (ref "D1") (pin "C") (pinfunction "C_C") (pintype "passive"))
      (node (ref "Q13") (pin "E") (pinfunction "E_E") (pintype "passive"))
      (node (ref "Q15") (pin "E") (pinfunction "E_E") (pintype "passive"))
      (node (ref "Q17") (pin "E") (pinfunction "E_E") (pintype "passive"))
      (node (ref "Q19") (pin "E") (pinfunction "E_E") (pintype "passive"))
      (node (ref "R12") (pin "2") (pinfunction "2_2") (pintype "passive"))
      (node (ref "R13") (pin "1") (pinfunction "1_1") (pintype "passive"))
      (node (ref "R14") (pin "1") (pinfunction "1_1") (pintype "passive"))
      (node (ref "R15") (pin "2") (pinfunction "2_2") (pintype "passive"))
      (node (ref "R3") (pin "2") (pinfunction "2_2") (pintype "passive"))
      (node (ref "R6") (pin "2") (pinfunction "2_2") (pintype "passive"))
      (node (ref "R9") (pin "2") (pinfunction "2_2") (pintype "passive"))
    )
    (net (code "65") (name "unconnected-(IC2-PA7-Pad18)") (class "Default")
      (node (ref "IC2") (pin "18") (pinfunction "PA7_18") (pintype "bidirectional"))
    )
    (net (code "66") (name "unconnected-(IC2-PA8-Pad28)") (class "Default")
      (node (ref "IC2") (pin "28") (pinfunction "PA8_28") (pintype "bidirectional"))
    )
    (net (code "67") (name "unconnected-(IC2-PA9-Pad29)") (class "Default")
      (node (ref "IC2") (pin "29") (pinfunction "PA9_29") (pintype "bidirectional"))
    )
    (net (code "68") (name "unconnected-(IC2-PA10-Pad32)") (class "Default")
      (node (ref "IC2") (pin "32") (pinfunction "PA10_32") (pintype "bidirectional"))
    )
    (net (code "69") (name "unconnected-(IC2-PA11[PA9]-Pad33)") (class "Default")
      (node (ref "IC2") (pin "33") (pinfunction "PA11[PA9]_33") (pintype "bidirectional"))
    )
    (net (code "70") (name "unconnected-(IC2-PA12_[PA10]-Pad34)") (class "Default")
      (node (ref "IC2") (pin "34") (pinfunction "PA12_[PA10]_34") (pintype "bidirectional"))
    )
    (net (code "71") (name "unconnected-(IC2-PB0-Pad19)") (class "Default")
      (node (ref "IC2") (pin "19") (pinfunction "PB0_19") (pintype "bidirectional"))
    )
    (net (code "72") (name "unconnected-(IC2-PB1-Pad20)") (class "Default")
      (node (ref "IC2") (pin "20") (pinfunction "PB1_20") (pintype "bidirectional"))
    )
    (net (code "73") (name "unconnected-(IC2-PB2-Pad21)") (class "Default")
      (node (ref "IC2") (pin "21") (pinfunction "PB2_21") (pintype "bidirectional"))
    )
    (net (code "74") (name "unconnected-(IC2-PB10-Pad22)") (class "Default")
      (node (ref "IC2") (pin "22") (pinfunction "PB10_22") (pintype "bidirectional"))
    )
    (net (code "75") (name "unconnected-(IC2-PB11-Pad23)") (class "Default")
      (node (ref "IC2") (pin "23") (pinfunction "PB11_23") (pintype "bidirectional"))
    )
    (net (code "76") (name "unconnected-(IC2-PB12-Pad24)") (class "Default")
      (node (ref "IC2") (pin "24") (pinfunction "PB12_24") (pintype "bidirectional"))
    )
    (net (code "77") (name "unconnected-(IC2-PB13-Pad25)") (class "Default")
      (node (ref "IC2") (pin "25") (pinfunction "PB13_25") (pintype "bidirectional"))
    )
    (net (code "78") (name "unconnected-(IC2-PB14-Pad26)") (class "Default")
      (node (ref "IC2") (pin "26") (pinfunction "PB14_26") (pintype "bidirectional"))
    )
    (net (code "79") (name "unconnected-(IC2-PB15-Pad27)") (class "Default")
      (node (ref "IC2") (pin "27") (pinfunction "PB15_27") (pintype "bidirectional"))
    )
    (net (code "80") (name "unconnected-(IC2-PC6-Pad30)") (class "Default")
      (node (ref "IC2") (pin "30") (pinfunction "PC6_30") (pintype "bidirectional"))
    )
    (net (code "81") (name "unconnected-(IC2-PC7-Pad31)") (class "Default")
      (node (ref "IC2") (pin "31") (pinfunction "PC7_31") (pintype "bidirectional"))
    )
    (net (code "82") (name "unconnected-(IC2-PF0-OSC_IN-Pad8)") (class "Default")
      (node (ref "IC2") (pin "8") (pinfunction "PF0-OSC_IN_8") (pintype "bidirectional"))
    )
    (net (code "83") (name "unconnected-(IC2-PF1-OSC_OUT-Pad9)") (class "Default")
      (node (ref "IC2") (pin "9") (pinfunction "PF1-OSC_OUT_9") (pintype "bidirectional"))
    )
    (net (code "84") (name "unconnected-(IC3-NC-Pad4)") (class "Default")
      (node (ref "IC3") (pin "4") (pinfunction "NC_4") (pintype "no_connect"))
    )
    (net (code "85") (name "unconnected-(J1-D+-Pad3)") (class "Default")
      (node (ref "J1") (pin "3") (pinfunction "D+_3") (pintype "passive"))
    )
    (net (code "86") (name "unconnected-(J1-D--Pad2)") (class "Default")
      (node (ref "J1") (pin "2") (pinfunction "D-_2") (pintype "passive"))
    )
    (net (code "87") (name "unconnected-(J1-ID-Pad4)") (class "Default")
      (node (ref "J1") (pin "4") (pinfunction "ID_4") (pintype "passive"))
    )
    (net (code "88") (name "unconnected-(N1-DECIMAL-Pad12)") (class "Default")
      (node (ref "N1") (pin "12") (pinfunction "DECIMAL_12") (pintype "bidirectional"))
    )
    (net (code "89") (name "unconnected-(N2-DECIMAL-Pad12)") (class "Default")
      (node (ref "N2") (pin "12") (pinfunction "DECIMAL_12") (pintype "bidirectional"))
    )
    (net (code "90") (name "unconnected-(N3-DECIMAL-Pad12)") (class "Default")
      (node (ref "N3") (pin "12") (pinfunction "DECIMAL_12") (pintype "bidirectional"))
    )
    (net (code "91") (name "unconnected-(N4-DECIMAL-Pad12)") (class "Default")
      (node (ref "N4") (pin "12") (pinfunction "DECIMAL_12") (pintype "bidirectional"))
    )
    (net (code "92") (name "unconnected-(S1-Pad2)") (class "Default")
      (node (ref "S1") (pin "2") (pinfunction "2_2") (pintype "passive"))
    )
  )
)
